# driver_motor.net
KiCad netlist of a schematic drawn in EAGLE
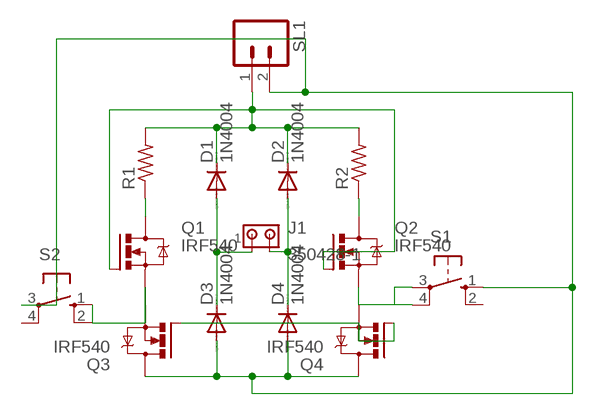
[diagram p0: schematic, sheet 1]

(export (version "E")
  (design (tool "Eeschema 10.0.6"))
  (components
    (comp (ref "D1")
      (value "1N4004")
      (footprint "eagle-import:DO41-10")
      (libsource (lib "eagle-import") (part "1N4004"))
    )
    (comp (ref "D2")
      (value "1N4004")
      (footprint "eagle-import:DO41-10")
      (libsource (lib "eagle-import") (part "1N4004"))
    )
    (comp (ref "D3")
      (value "1N4004")
      (footprint "eagle-import:DO41-10")
      (libsource (lib "eagle-import") (part "1N4004"))
    )
    (comp (ref "D4")
      (value "1N4004")
      (footprint "eagle-import:DO41-10")
      (libsource (lib "eagle-import") (part "1N4004"))
    )
    (comp (ref "J1")
      (value "350428-1")
      (footprint "eagle-import:350428-1")
      (libsource (lib "eagle-import") (part "350428-1"))
    )
    (comp (ref "Q1")
      (value "IRF540")
      (footprint "eagle-import:TO220BV")
      (libsource (lib "eagle-import") (part "IRF540"))
    )
    (comp (ref "Q2")
      (value "IRF540")
      (footprint "eagle-import:TO220BV")
      (libsource (lib "eagle-import") (part "IRF540"))
    )
    (comp (ref "Q3")
      (value "IRF540")
      (footprint "eagle-import:TO220BV")
      (libsource (lib "eagle-import") (part "IRF540"))
    )
    (comp (ref "Q4")
      (value "IRF540")
      (footprint "eagle-import:TO220BV")
      (libsource (lib "eagle-import") (part "IRF540"))
    )
    (comp (ref "R1")
      (value "R-US_0207/7")
      (footprint "eagle-import:0207_7")
      (libsource (lib "eagle-import") (part "R-US_0207/7"))
    )
    (comp (ref "R2")
      (value "R-US_0207/7")
      (footprint "eagle-import:0207_7")
      (libsource (lib "eagle-import") (part "R-US_0207/7"))
    )
    (comp (ref "S1")
      (value "10-XX")
      (footprint "eagle-import:B3F-10XX")
      (fields (field (name "MPN") "B3F-1000"))
      (libsource (lib "eagle-import") (part "10-XX"))
    )
    (comp (ref "S2")
      (value "10-XX")
      (footprint "eagle-import:B3F-10XX")
      (fields (field (name "MPN") "B3F-1000"))
      (libsource (lib "eagle-import") (part "10-XX"))
    )
    (comp (ref "SL1")
      (value "M02")
      (footprint "eagle-import:02P")
      (libsource (lib "eagle-import") (part "M02"))
    )
  )
  (nets
    (net (code "1") (name "Net-(D1-PadA)") (class "Default")
      (node (ref "D1") (pin "A") (pinfunction "A_A") (pintype "passive"))
      (node (ref "D3") (pin "C") (pinfunction "C_C") (pintype "passive"))
      (node (ref "J1") (pin "1") (pinfunction "1_1") (pintype "passive"))
    )
    (net (code "2") (name "Net-(D1-PadC)") (class "Default")
      (node (ref "D1") (pin "C") (pinfunction "C_C") (pintype "passive"))
      (node (ref "D2") (pin "C") (pinfunction "C_C") (pintype "passive"))
      (node (ref "Q1") (pin "G") (pinfunction "G_G") (pintype "passive"))
      (node (ref "Q2") (pin "G") (pinfunction "G_G") (pintype "passive"))
      (node (ref "R1") (pin "2") (pinfunction "2_2") (pintype "passive"))
      (node (ref "R2") (pin "2") (pinfunction "2_2") (pintype "passive"))
      (node (ref "SL1") (pin "1") (pinfunction "1_1") (pintype "passive"))
    )
    (net (code "3") (name "Net-(D2-PadA)") (class "Default")
      (node (ref "D2") (pin "A") (pinfunction "A_A") (pintype "passive"))
      (node (ref "D4") (pin "C") (pinfunction "C_C") (pintype "passive"))
      (node (ref "J1") (pin "2") (pinfunction "2_2") (pintype "passive"))
    )
    (net (code "4") (name "Net-(Q1-PadD)") (class "Default")
      (node (ref "Q1") (pin "D") (pinfunction "D_D") (pintype "passive"))
      (node (ref "R1") (pin "1") (pinfunction "1_1") (pintype "passive"))
    )
    (net (code "5") (name "Net-(Q2-PadD)") (class "Default")
      (node (ref "Q2") (pin "D") (pinfunction "D_D") (pintype "passive"))
      (node (ref "R2") (pin "1") (pinfunction "1_1") (pintype "passive"))
    )
    (net (code "6") (name "Net-(Q3-PadG)") (class "Default")
      (node (ref "Q3") (pin "G") (pinfunction "G_G") (pintype "passive"))
      (node (ref "Q4") (pin "G") (pinfunction "G_G") (pintype "passive"))
    )
    (net (code "7") (name "Net-(S1-P)") (class "Default")
      (node (ref "Q2") (pin "S") (pinfunction "S_S") (pintype "passive"))
      (node (ref "Q4") (pin "S") (pinfunction "S_S") (pintype "passive"))
      (node (ref "S1") (pin "3") (pinfunction "P_3") (pintype "passive"))
      (node (ref "S1") (pin "4") (pinfunction "P1_4") (pintype "passive"))
    )
    (net (code "8") (name "Net-(S1-S)") (class "Default")
      (node (ref "D3") (pin "A") (pinfunction "A_A") (pintype "passive"))
      (node (ref "D4") (pin "A") (pinfunction "A_A") (pintype "passive"))
      (node (ref "Q3") (pin "D") (pinfunction "D_D") (pintype "passive"))
      (node (ref "Q4") (pin "D") (pinfunction "D_D") (pintype "passive"))
      (node (ref "S1") (pin "1") (pinfunction "S_1") (pintype "passive"))
      (node (ref "S2") (pin "3") (pinfunction "P_3") (pintype "passive"))
      (node (ref "SL1") (pin "2") (pinfunction "2_2") (pintype "passive"))
    )
    (net (code "9") (name "Net-(S2-S)") (class "Default")
      (node (ref "Q1") (pin "S") (pinfunction "S_S") (pintype "passive"))
      (node (ref "Q3") (pin "S") (pinfunction "S_S") (pintype "passive"))
      (node (ref "S2") (pin "1") (pinfunction "S_1") (pintype "passive"))
      (node (ref "S2") (pin "2") (pinfunction "S1_2") (pintype "passive"))
    )
    (net (code "10") (name "unconnected-(S1-S1-Pad2)") (class "Default")
      (node (ref "S1") (pin "2") (pinfunction "S1_2") (pintype "passive"))
    )
    (net (code "11") (name "unconnected-(S2-P1-Pad4)") (class "Default")
      (node (ref "S2") (pin "4") (pinfunction "P1_4") (pintype "passive"))
    )
  )
)
